# ckt1.net
KiCad netlist of a schematic drawn in EAGLE
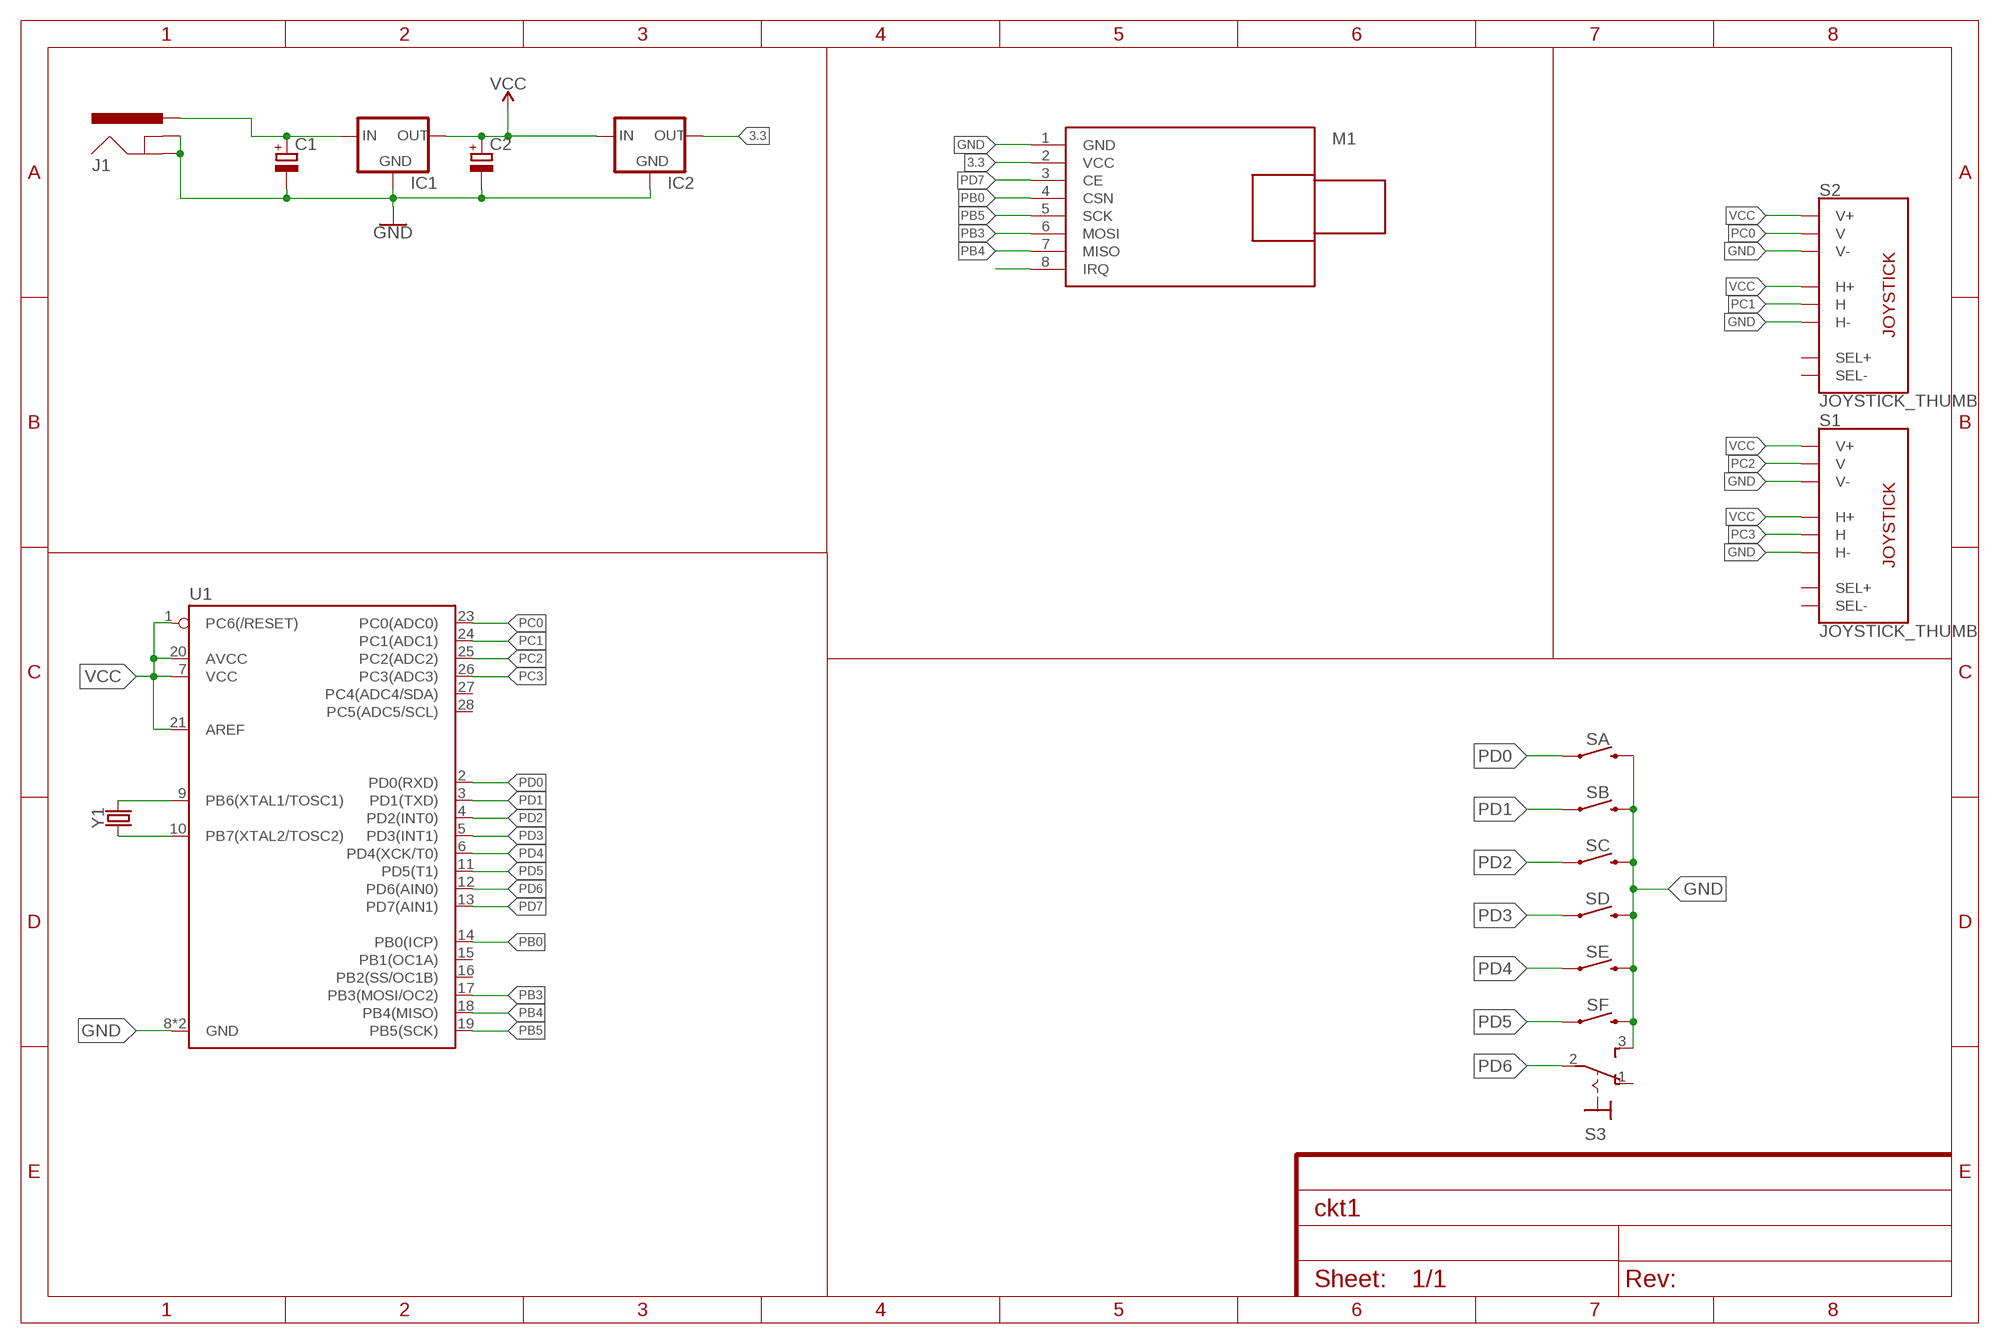
[diagram p0: schematic, sheet 1]

(export (version "E")
  (design (tool "Eeschema 10.0.6"))
  (components
    (comp (ref "C1")
      (value "CPOL-EUE2-5")
      (footprint "eagle-import:E2-5")
      (libsource (lib "eagle-import") (part "CPOL-EUE2-5"))
    )
    (comp (ref "C2")
      (value "CPOL-EUE2-5")
      (footprint "eagle-import:E2-5")
      (libsource (lib "eagle-import") (part "CPOL-EUE2-5"))
    )
    (comp (ref "IC1")
      (value "78XXS")
      (footprint "eagle-import:78XXS")
      (libsource (lib "eagle-import") (part "78XXS"))
    )
    (comp (ref "IC2")
      (value "78XXS")
      (footprint "eagle-import:78XXS")
      (libsource (lib "eagle-import") (part "78XXS"))
    )
    (comp (ref "J1")
      (value "POWER_JACKSLT")
      (footprint "eagle-import:POWER_JACK_SLOT")
      (libsource (lib "eagle-import") (part "POWER_JACKSLT"))
    )
    (comp (ref "M1")
      (value "WIRELESS-NRF24L01-PA-EXT")
      (footprint "eagle-import:WIRELESS-NRF24L01-PA-EXT")
      (libsource (lib "eagle-import") (part "WIRELESS-NRF24L01-PA-EXT"))
    )
    (comp (ref "S1")
      (value "JOYSTICK_THUMB")
      (footprint "eagle-import:JOYSTICK")
      (libsource (lib "eagle-import") (part "JOYSTICK_THUMB"))
    )
    (comp (ref "S2")
      (value "JOYSTICK_THUMB")
      (footprint "eagle-import:JOYSTICK")
      (libsource (lib "eagle-import") (part "JOYSTICK_THUMB"))
    )
    (comp (ref "S3")
      (value "320-916")
      (footprint "eagle-import:320-916")
      (libsource (lib "eagle-import") (part "320-916"))
    )
    (comp (ref "SA")
      (value "MOMENTARY-SWITCH-SPST-PTH-6.0MM")
      (footprint "eagle-import:TACTILE_SWITCH_PTH_6.0MM")
      (libsource (lib "eagle-import") (part "MOMENTARY-SWITCH-SPST-PTH-6.0MM"))
    )
    (comp (ref "SB")
      (value "MOMENTARY-SWITCH-SPST-PTH-6.0MM")
      (footprint "eagle-import:TACTILE_SWITCH_PTH_6.0MM")
      (libsource (lib "eagle-import") (part "MOMENTARY-SWITCH-SPST-PTH-6.0MM"))
    )
    (comp (ref "SC")
      (value "MOMENTARY-SWITCH-SPST-PTH-6.0MM")
      (footprint "eagle-import:TACTILE_SWITCH_PTH_6.0MM")
      (libsource (lib "eagle-import") (part "MOMENTARY-SWITCH-SPST-PTH-6.0MM"))
    )
    (comp (ref "SD")
      (value "MOMENTARY-SWITCH-SPST-PTH-6.0MM")
      (footprint "eagle-import:TACTILE_SWITCH_PTH_6.0MM")
      (libsource (lib "eagle-import") (part "MOMENTARY-SWITCH-SPST-PTH-6.0MM"))
    )
    (comp (ref "SE")
      (value "MOMENTARY-SWITCH-SPST-PTH-6.0MM")
      (footprint "eagle-import:TACTILE_SWITCH_PTH_6.0MM")
      (libsource (lib "eagle-import") (part "MOMENTARY-SWITCH-SPST-PTH-6.0MM"))
    )
    (comp (ref "SF")
      (value "MOMENTARY-SWITCH-SPST-PTH-6.0MM")
      (footprint "eagle-import:TACTILE_SWITCH_PTH_6.0MM")
      (libsource (lib "eagle-import") (part "MOMENTARY-SWITCH-SPST-PTH-6.0MM"))
    )
    (comp (ref "U1")
      (value "328P")
      (footprint "eagle-import:DIP28")
      (libsource (lib "eagle-import") (part "ATMEGA328P_PDIP"))
    )
    (comp (ref "Y1")
      (value "CRYSTALPTH-HC49US")
      (footprint "eagle-import:HC49US")
      (libsource (lib "eagle-import") (part "CRYSTALPTH-HC49US"))
    )
  )
  (nets
    (net (code "1") (name "3.3") (class "Default")
      (node (ref "IC2") (pin "OUT") (pinfunction "OUT_OUT") (pintype "passive"))
      (node (ref "M1") (pin "2") (pinfunction "VCC_2") (pintype "power_in"))
    )
    (net (code "2") (name "GND") (class "Default")
      (node (ref "C1") (pin "-") (pinfunction "-_-") (pintype "passive"))
      (node (ref "C2") (pin "-") (pinfunction "-_-") (pintype "passive"))
      (node (ref "IC1") (pin "GND") (pinfunction "GND_GND") (pintype "input"))
      (node (ref "IC2") (pin "GND") (pinfunction "GND_GND") (pintype "input"))
      (node (ref "J1") (pin "GND@1") (pinfunction "GNDBREAK_GND@1") (pintype "bidirectional"))
      (node (ref "J1") (pin "GND@2") (pinfunction "GND_GND@2") (pintype "bidirectional"))
      (node (ref "M1") (pin "1") (pinfunction "GND_1") (pintype "power_in"))
      (node (ref "S1") (pin "H3") (pinfunction "H-_H3") (pintype "bidirectional"))
      (node (ref "S1") (pin "V3") (pinfunction "V-_V3") (pintype "bidirectional"))
      (node (ref "S2") (pin "H3") (pinfunction "H-_H3") (pintype "bidirectional"))
      (node (ref "S2") (pin "V3") (pinfunction "V-_V3") (pintype "bidirectional"))
      (node (ref "S3") (pin "3") (pinfunction "S_3") (pintype "passive"))
      (node (ref "SA") (pin "3") (pinfunction "2_3") (pintype "passive"))
      (node (ref "SB") (pin "3") (pinfunction "2_3") (pintype "passive"))
      (node (ref "SC") (pin "3") (pinfunction "2_3") (pintype "passive"))
      (node (ref "SD") (pin "3") (pinfunction "2_3") (pintype "passive"))
      (node (ref "SE") (pin "3") (pinfunction "2_3") (pintype "passive"))
      (node (ref "SF") (pin "3") (pinfunction "2_3") (pintype "passive"))
      (node (ref "U1") (pin "22") (pinfunction "GND_22") (pintype "bidirectional"))
      (node (ref "U1") (pin "8") (pinfunction "GND_8") (pintype "bidirectional"))
    )
    (net (code "3") (name "Net-(C1-Pad+)") (class "Default")
      (node (ref "C1") (pin "+") (pinfunction "+_+") (pintype "passive"))
      (node (ref "IC1") (pin "IN") (pinfunction "IN_IN") (pintype "input"))
      (node (ref "J1") (pin "PWR") (pinfunction "PWR_PWR") (pintype "bidirectional"))
    )
    (net (code "4") (name "Net-(U1-PB6(XTAL1{slash}TOSC1))") (class "Default")
      (node (ref "U1") (pin "9") (pinfunction "PB6(XTAL1/TOSC1)_9") (pintype "bidirectional"))
      (node (ref "Y1") (pin "2") (pinfunction "2_2") (pintype "passive"))
    )
    (net (code "5") (name "Net-(U1-PB7(XTAL2{slash}TOSC2))") (class "Default")
      (node (ref "U1") (pin "10") (pinfunction "PB7(XTAL2/TOSC2)_10") (pintype "bidirectional"))
      (node (ref "Y1") (pin "1") (pinfunction "1_1") (pintype "passive"))
    )
    (net (code "6") (name "PB0") (class "Default")
      (node (ref "M1") (pin "4") (pinfunction "CSN_4") (pintype "bidirectional"))
      (node (ref "U1") (pin "14") (pinfunction "PB0(ICP)_14") (pintype "bidirectional"))
    )
    (net (code "7") (name "PB3") (class "Default")
      (node (ref "M1") (pin "6") (pinfunction "MOSI_6") (pintype "bidirectional"))
      (node (ref "U1") (pin "17") (pinfunction "PB3(MOSI/OC2)_17") (pintype "bidirectional"))
    )
    (net (code "8") (name "PB4") (class "Default")
      (node (ref "M1") (pin "7") (pinfunction "MISO_7") (pintype "bidirectional"))
      (node (ref "U1") (pin "18") (pinfunction "PB4(MISO)_18") (pintype "bidirectional"))
    )
    (net (code "9") (name "PB5") (class "Default")
      (node (ref "M1") (pin "5") (pinfunction "SCK_5") (pintype "bidirectional"))
      (node (ref "U1") (pin "19") (pinfunction "PB5(SCK)_19") (pintype "bidirectional"))
    )
    (net (code "10") (name "PC0") (class "Default")
      (node (ref "S2") (pin "V2") (pinfunction "V_V2") (pintype "bidirectional"))
      (node (ref "U1") (pin "23") (pinfunction "PC0(ADC0)_23") (pintype "bidirectional"))
    )
    (net (code "11") (name "PC1") (class "Default")
      (node (ref "S2") (pin "H2") (pinfunction "H_H2") (pintype "bidirectional"))
      (node (ref "U1") (pin "24") (pinfunction "PC1(ADC1)_24") (pintype "bidirectional"))
    )
    (net (code "12") (name "PC2") (class "Default")
      (node (ref "S1") (pin "V2") (pinfunction "V_V2") (pintype "bidirectional"))
      (node (ref "U1") (pin "25") (pinfunction "PC2(ADC2)_25") (pintype "bidirectional"))
    )
    (net (code "13") (name "PC3") (class "Default")
      (node (ref "S1") (pin "H2") (pinfunction "H_H2") (pintype "bidirectional"))
      (node (ref "U1") (pin "26") (pinfunction "PC3(ADC3)_26") (pintype "bidirectional"))
    )
    (net (code "14") (name "PD0") (class "Default")
      (node (ref "SA") (pin "1") (pinfunction "1_1") (pintype "passive"))
      (node (ref "U1") (pin "2") (pinfunction "PD0(RXD)_2") (pintype "bidirectional"))
    )
    (net (code "15") (name "PD1") (class "Default")
      (node (ref "SB") (pin "1") (pinfunction "1_1") (pintype "passive"))
      (node (ref "U1") (pin "3") (pinfunction "PD1(TXD)_3") (pintype "bidirectional"))
    )
    (net (code "16") (name "PD2") (class "Default")
      (node (ref "SC") (pin "1") (pinfunction "1_1") (pintype "passive"))
      (node (ref "U1") (pin "4") (pinfunction "PD2(INT0)_4") (pintype "bidirectional"))
    )
    (net (code "17") (name "PD3") (class "Default")
      (node (ref "SD") (pin "1") (pinfunction "1_1") (pintype "passive"))
      (node (ref "U1") (pin "5") (pinfunction "PD3(INT1)_5") (pintype "bidirectional"))
    )
    (net (code "18") (name "PD4") (class "Default")
      (node (ref "SE") (pin "1") (pinfunction "1_1") (pintype "passive"))
      (node (ref "U1") (pin "6") (pinfunction "PD4(XCK/T0)_6") (pintype "bidirectional"))
    )
    (net (code "19") (name "PD5") (class "Default")
      (node (ref "SF") (pin "1") (pinfunction "1_1") (pintype "passive"))
      (node (ref "U1") (pin "11") (pinfunction "PD5(T1)_11") (pintype "bidirectional"))
    )
    (net (code "20") (name "PD6") (class "Default")
      (node (ref "S3") (pin "2") (pinfunction "P_2") (pintype "passive"))
      (node (ref "U1") (pin "12") (pinfunction "PD6(AIN0)_12") (pintype "bidirectional"))
    )
    (net (code "21") (name "PD7") (class "Default")
      (node (ref "M1") (pin "3") (pinfunction "CE_3") (pintype "bidirectional"))
      (node (ref "U1") (pin "13") (pinfunction "PD7(AIN1)_13") (pintype "bidirectional"))
    )
    (net (code "22") (name "VCC") (class "Default")
      (node (ref "C2") (pin "+") (pinfunction "+_+") (pintype "passive"))
      (node (ref "IC1") (pin "OUT") (pinfunction "OUT_OUT") (pintype "passive"))
      (node (ref "IC2") (pin "IN") (pinfunction "IN_IN") (pintype "input"))
      (node (ref "S1") (pin "H1") (pinfunction "H+_H1") (pintype "bidirectional"))
      (node (ref "S1") (pin "V1") (pinfunction "V+_V1") (pintype "bidirectional"))
      (node (ref "S2") (pin "H1") (pinfunction "H+_H1") (pintype "bidirectional"))
      (node (ref "S2") (pin "V1") (pinfunction "V+_V1") (pintype "bidirectional"))
      (node (ref "U1") (pin "1") (pinfunction "PC6(/RESET)_1") (pintype "bidirectional"))
      (node (ref "U1") (pin "20") (pinfunction "AVCC_20") (pintype "bidirectional"))
      (node (ref "U1") (pin "21") (pinfunction "AREF_21") (pintype "bidirectional"))
      (node (ref "U1") (pin "7") (pinfunction "VCC_7") (pintype "bidirectional"))
    )
    (net (code "23") (name "unconnected-(M1-IRQ-Pad8)") (class "Default")
      (node (ref "M1") (pin "8") (pinfunction "IRQ_8") (pintype "bidirectional"))
    )
    (net (code "24") (name "unconnected-(S1-SEL+-PadB1A)") (class "Default")
      (node (ref "S1") (pin "B1A") (pinfunction "SEL+_B1A") (pintype "bidirectional"))
    )
    (net (code "25") (name "unconnected-(S1-SEL--PadB2A)") (class "Default")
      (node (ref "S1") (pin "B2A") (pinfunction "SEL-_B2A") (pintype "bidirectional"))
    )
    (net (code "26") (name "unconnected-(S2-SEL+-PadB1A)") (class "Default")
      (node (ref "S2") (pin "B1A") (pinfunction "SEL+_B1A") (pintype "bidirectional"))
    )
    (net (code "27") (name "unconnected-(S2-SEL--PadB2A)") (class "Default")
      (node (ref "S2") (pin "B2A") (pinfunction "SEL-_B2A") (pintype "bidirectional"))
    )
    (net (code "28") (name "unconnected-(S3-O-Pad1)") (class "Default")
      (node (ref "S3") (pin "1") (pinfunction "O_1") (pintype "passive"))
    )
    (net (code "29") (name "unconnected-(U1-PB1(OC1A)-Pad15)") (class "Default")
      (node (ref "U1") (pin "15") (pinfunction "PB1(OC1A)_15") (pintype "bidirectional"))
    )
    (net (code "30") (name "unconnected-(U1-PB2(SS{slash}OC1B)-Pad16)") (class "Default")
      (node (ref "U1") (pin "16") (pinfunction "PB2(SS/OC1B)_16") (pintype "bidirectional"))
    )
    (net (code "31") (name "unconnected-(U1-PC4(ADC4{slash}SDA)-Pad27)") (class "Default")
      (node (ref "U1") (pin "27") (pinfunction "PC4(ADC4/SDA)_27") (pintype "bidirectional"))
    )
    (net (code "32") (name "unconnected-(U1-PC5(ADC5{slash}SCL)-Pad28)") (class "Default")
      (node (ref "U1") (pin "28") (pinfunction "PC5(ADC5/SCL)_28") (pintype "bidirectional"))
    )
  )
)
